# TIA.net
KiCad netlist of a schematic drawn in Altium Designer
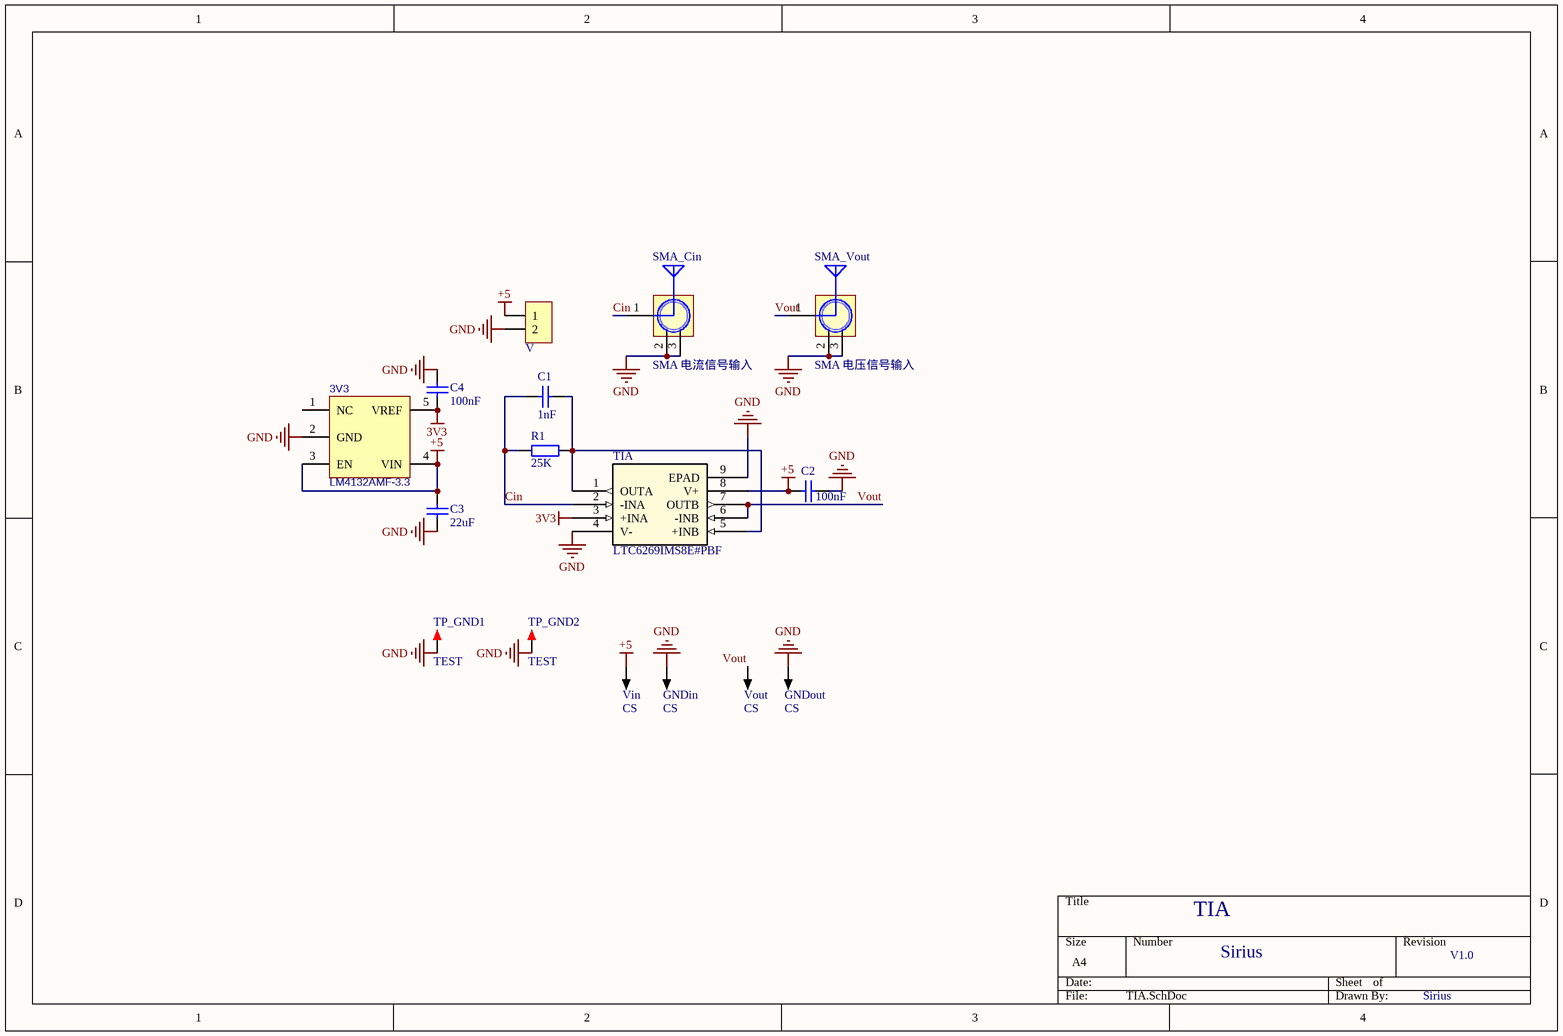
[diagram p0: TIA.SchDoc]

(export (version "E")
  (design (tool "Eeschema 10.0.6"))
  (components
    (comp (ref "3V3")
      (value "LM4132AMF-3.3")
      (footprint "SOT-23-5")
      (description "基准电压源 3V3")
      (libsource (lib "Extra Sch") (part "LM4132AMF-3.3"))
    )
    (comp (ref "C1")
      (value "1nF")
      (footprint "C0603_L")
      (description "贴片电容")
      (libsource (lib "0.1 - 电阻-电容-电感-晶振-晶体-磁珠-电位器") (part "C"))
    )
    (comp (ref "C2")
      (value "100nF")
      (footprint "C0603_L")
      (description "贴片电容")
      (libsource (lib "0.1 - 电阻-电容-电感-晶振-晶体-磁珠-电位器") (part "C"))
    )
    (comp (ref "C3")
      (value "22uF")
      (footprint "C0603_L")
      (description "贴片电容")
      (libsource (lib "0.1 - 电阻-电容-电感-晶振-晶体-磁珠-电位器") (part "C"))
    )
    (comp (ref "C4")
      (value "100nF")
      (footprint "C0603_L")
      (description "贴片电容")
      (libsource (lib "0.1 - 电阻-电容-电感-晶振-晶体-磁珠-电位器") (part "C"))
    )
    (comp (ref "GNDin")
      (value "CS")
      (footprint "R100")
      (description "探针焊盘")
      (libsource (lib "0.5 - 按键-开关-蜂鸣器-保险丝-电池-测试点-Mark点") (part "CS"))
    )
    (comp (ref "GNDout")
      (value "CS")
      (footprint "R100")
      (description "探针焊盘")
      (libsource (lib "0.5 - 按键-开关-蜂鸣器-保险丝-电池-测试点-Mark点") (part "CS"))
    )
    (comp (ref "R1")
      (value "25K")
      (footprint "R0603_L")
      (description "贴片电阻")
      (libsource (lib "0.1 - 电阻-电容-电感-晶振-晶体-磁珠-电位器") (part "R"))
    )
    (comp (ref "SMA_Cin")
      (value "SMA 电流信号输入")
      (footprint "SMA_FR")
      (description "SMA-2.4G射频天线接口")
      (libsource (lib "1.7 - WiFi天线-SMA射频座") (part "SMA"))
    )
    (comp (ref "SMA_Vout")
      (value "SMA 电压信号输入")
      (footprint "SMA_FR")
      (description "SMA-2.4G射频天线接口")
      (libsource (lib "1.7 - WiFi天线-SMA射频座") (part "SMA"))
    )
    (comp (ref "TIA")
      (value "LTC6269IMS8E#PBF")
      (footprint "MSE_8_LIT-L")
      (description "低偏置电流运放")
      (fields (field (name "COPYRIGHT") "Copyright (C) 2022 Ultra Librarian. All rights reserved."))
      (libsource (lib "Extra Sch") (part "LTC6269IMS8E#PBF"))
    )
    (comp (ref "TP_GND1")
      (value "TEST")
      (footprint "TEST 1.6")
      (description "测试点")
      (libsource (lib "0.5 - 按键-开关-蜂鸣器-保险丝-电池-测试点-Mark点") (part "TEST"))
    )
    (comp (ref "TP_GND2")
      (value "TEST")
      (footprint "TEST 1.6")
      (description "测试点")
      (libsource (lib "0.5 - 按键-开关-蜂鸣器-保险丝-电池-测试点-Mark点") (part "TEST"))
    )
    (comp (ref "V")
      (value "HDR-1X2")
      (footprint "HDR2.54-LI-2P")
      (description "2P接插件")
      (libsource (lib "5.5 - 2.54mm(100mil)连接器(XH2.54)") (part "Header 2"))
    )
    (comp (ref "Vin")
      (value "CS")
      (footprint "R100")
      (description "探针焊盘")
      (libsource (lib "0.5 - 按键-开关-蜂鸣器-保险丝-电池-测试点-Mark点") (part "CS"))
    )
    (comp (ref "Vout")
      (value "CS")
      (footprint "R100")
      (description "探针焊盘")
      (libsource (lib "0.5 - 按键-开关-蜂鸣器-保险丝-电池-测试点-Mark点") (part "CS"))
    )
  )
  (nets
    (net (code "1") (name "+5") (class "Default")
      (node (ref "3V3") (pin "3") (pinfunction "EN_3") (pintype "passive"))
      (node (ref "3V3") (pin "4") (pinfunction "VIN_4") (pintype "passive"))
      (node (ref "C2") (pin "1") (pinfunction "1_1") (pintype "passive"))
      (node (ref "C3") (pin "1") (pinfunction "1_1") (pintype "passive"))
      (node (ref "TIA") (pin "8") (pinfunction "V+_8") (pintype "passive"))
      (node (ref "V") (pin "1") (pinfunction "1_1") (pintype "passive"))
      (node (ref "Vin") (pin "1") (pinfunction "1_1") (pintype "passive"))
    )
    (net (code "2") (name "/Cin") (class "Default")
      (node (ref "C1") (pin "2") (pinfunction "2_2") (pintype "passive"))
      (node (ref "R1") (pin "1") (pinfunction "1_1") (pintype "passive"))
      (node (ref "SMA_Cin") (pin "1") (pinfunction "ANT_1") (pintype "passive"))
      (node (ref "TIA") (pin "2") (pinfunction "-INA_2") (pintype "input"))
    )
    (net (code "3") (name "/Vout") (class "Default")
      (node (ref "SMA_Vout") (pin "1") (pinfunction "ANT_1") (pintype "passive"))
      (node (ref "TIA") (pin "6") (pinfunction "-INB_6") (pintype "input"))
      (node (ref "TIA") (pin "7") (pinfunction "OUTB_7") (pintype "output"))
      (node (ref "Vout") (pin "1") (pinfunction "1_1") (pintype "passive"))
    )
    (net (code "4") (name "3V3") (class "Default")
      (node (ref "3V3") (pin "5") (pinfunction "VREF_5") (pintype "passive"))
      (node (ref "C4") (pin "2") (pinfunction "2_2") (pintype "passive"))
      (node (ref "TIA") (pin "3") (pinfunction "+INA_3") (pintype "input"))
    )
    (net (code "5") (name "GND") (class "Default")
      (node (ref "3V3") (pin "2") (pinfunction "GND_2") (pintype "passive"))
      (node (ref "C2") (pin "2") (pinfunction "2_2") (pintype "passive"))
      (node (ref "C3") (pin "2") (pinfunction "2_2") (pintype "passive"))
      (node (ref "C4") (pin "1") (pinfunction "1_1") (pintype "passive"))
      (node (ref "GNDin") (pin "1") (pinfunction "1_1") (pintype "passive"))
      (node (ref "GNDout") (pin "1") (pinfunction "1_1") (pintype "passive"))
      (node (ref "SMA_Cin") (pin "2") (pinfunction "GND_2") (pintype "passive"))
      (node (ref "SMA_Cin") (pin "3") (pinfunction "GND_3") (pintype "passive"))
      (node (ref "SMA_Vout") (pin "2") (pinfunction "GND_2") (pintype "passive"))
      (node (ref "SMA_Vout") (pin "3") (pinfunction "GND_3") (pintype "passive"))
      (node (ref "TIA") (pin "4") (pinfunction "V-_4") (pintype "passive"))
      (node (ref "TIA") (pin "9") (pinfunction "EPAD_9") (pintype "passive"))
      (node (ref "TP_GND1") (pin "1") (pinfunction "1_1") (pintype "passive"))
      (node (ref "TP_GND2") (pin "1") (pinfunction "1_1") (pintype "passive"))
      (node (ref "V") (pin "2") (pinfunction "2_2") (pintype "passive"))
    )
    (net (code "6") (name "Net-(TIA-+INB)") (class "Default")
      (node (ref "C1") (pin "1") (pinfunction "1_1") (pintype "passive"))
      (node (ref "R1") (pin "2") (pinfunction "2_2") (pintype "passive"))
      (node (ref "TIA") (pin "1") (pinfunction "OUTA_1") (pintype "output"))
      (node (ref "TIA") (pin "5") (pinfunction "+INB_5") (pintype "input"))
    )
    (net (code "7") (name "unconnected-(3V3-NC-Pad1)") (class "Default")
      (node (ref "3V3") (pin "1") (pinfunction "NC_1") (pintype "passive"))
    )
  )
)
